# SmartDorm-ESP32.net
KiCad netlist of a schematic drawn in EasyEDA Pro
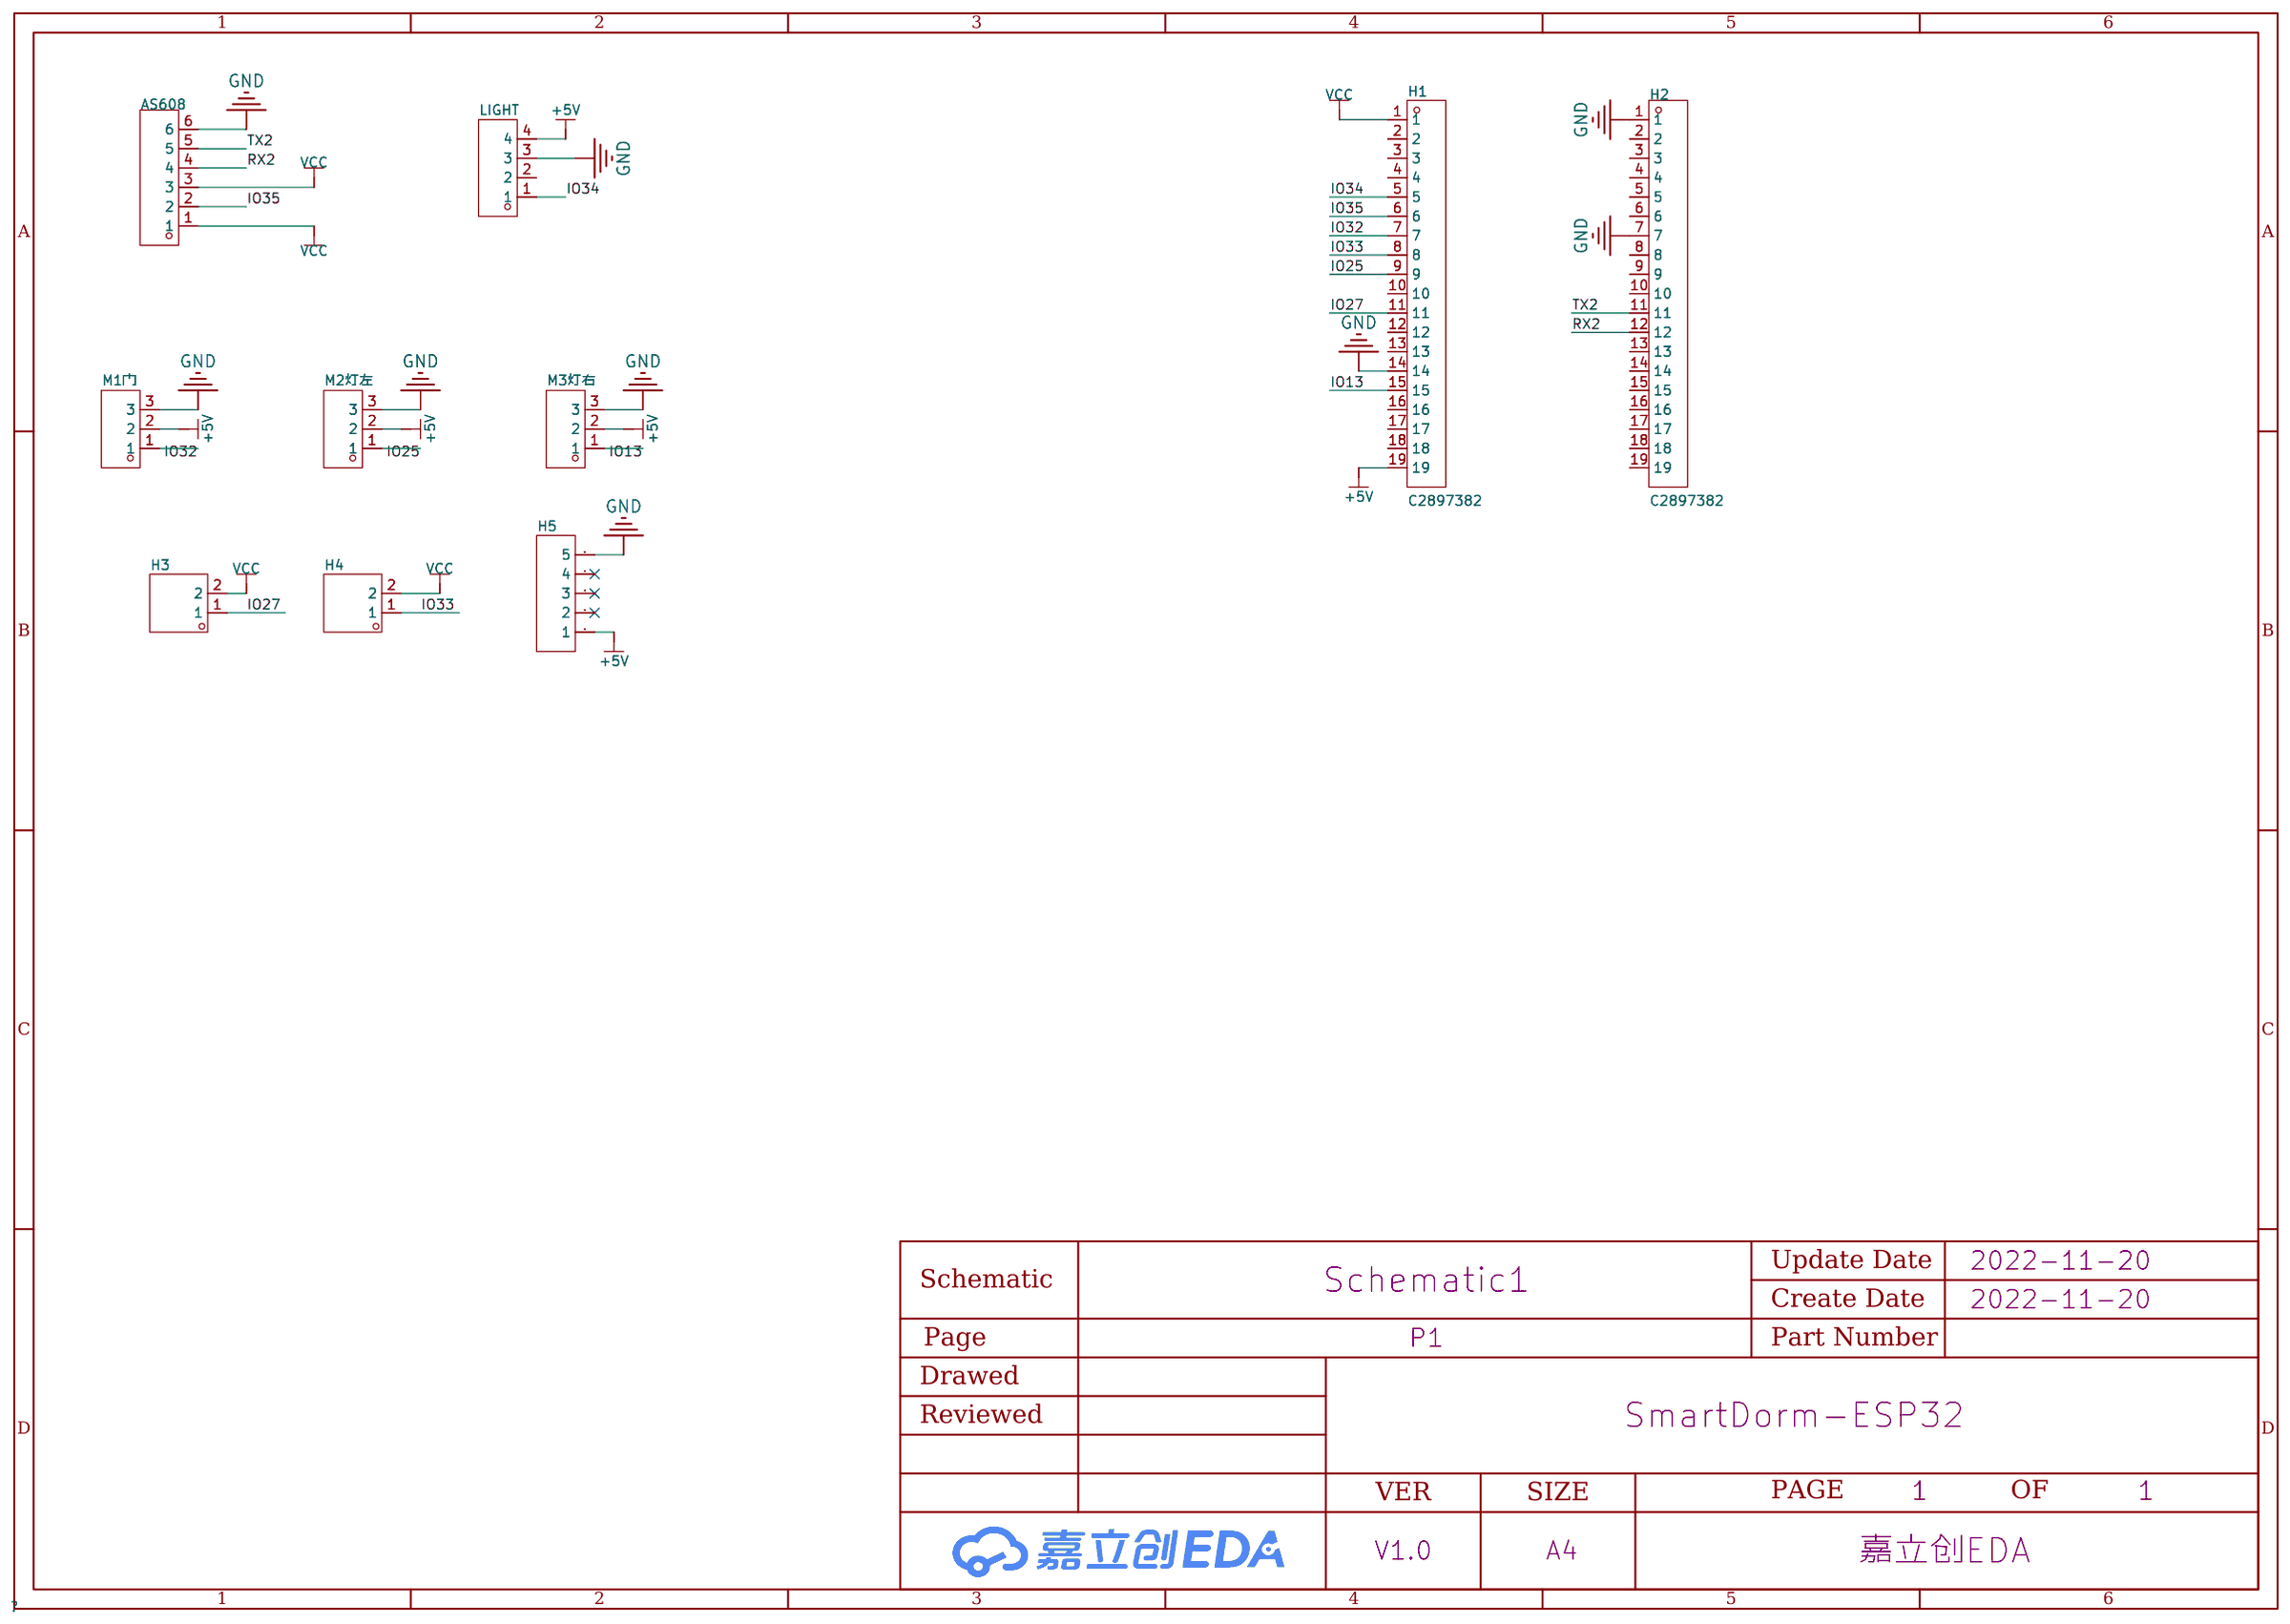
[diagram p0: schematic sheet]

(export (version "E")
  (design (tool "Eeschema 10.0.6"))
  (components
    (comp (ref "AS608")
      (value "~")
      (footprint "easyedapro:HDR-TH_6P-P2.54-V-F")
      (libsource (lib "easyedapro") (part "Header-Female-2.54_1x6"))
    )
    (comp (ref "H1")
      (value "C2897382")
      (footprint "easyedapro:HDR-TH_19P-P2.54-V-F")
      (libsource (lib "easyedapro") (part "HDR-F_2.54_1x19P"))
    )
    (comp (ref "H2")
      (value "C2897382")
      (footprint "easyedapro:HDR-TH_19P-P2.54-V-F")
      (libsource (lib "easyedapro") (part "HDR-F_2.54_1x19P"))
    )
    (comp (ref "H3")
      (value "~")
      (footprint "easyedapro:HDR-TH_2P-P2.54-V-M-1")
      (libsource (lib "easyedapro") (part "210S-1*2P L=11.6MMGold-plated black"))
    )
    (comp (ref "H4")
      (value "~")
      (footprint "easyedapro:HDR-TH_2P-P2.54-V-M-1")
      (libsource (lib "easyedapro") (part "210S-1*2P L=11.6MMGold-plated black"))
    )
    (comp (ref "H5")
      (value "~")
      (footprint "easyedapro:HDR-TH_5P-P2.54-V-F")
      (libsource (lib "easyedapro") (part "Header-Female-2.54_1x5"))
    )
    (comp (ref "LIGHT")
      (value "~")
      (footprint "easyedapro:HDR-TH_4P-P2.54-V-F")
      (libsource (lib "easyedapro") (part "2.54-1*4P母"))
    )
    (comp (ref "M1门")
      (value "~")
      (footprint "easyedapro:HDR-TH_3P-P2.54-V-M")
      (libsource (lib "easyedapro") (part "PZ254V-11-03P_C2937625"))
    )
    (comp (ref "M2灯左")
      (value "~")
      (footprint "easyedapro:HDR-TH_3P-P2.54-V-M")
      (libsource (lib "easyedapro") (part "PZ254V-11-03P_C2937625"))
    )
    (comp (ref "M3灯右")
      (value "~")
      (footprint "easyedapro:HDR-TH_3P-P2.54-V-M")
      (libsource (lib "easyedapro") (part "PZ254V-11-03P_C2937625"))
    )
  )
  (nets
    (net (code "1") (name "+5V") (class "Default")
      (node (ref "H1") (pin "19") (pinfunction "19_19") (pintype "input"))
      (node (ref "H5") (pin "1") (pinfunction "1_1") (pintype "input"))
      (node (ref "LIGHT") (pin "4") (pinfunction "4_4") (pintype "input"))
      (node (ref "M1门") (pin "2") (pinfunction "2_2") (pintype "input"))
      (node (ref "M2灯左") (pin "2") (pinfunction "2_2") (pintype "input"))
      (node (ref "M3灯右") (pin "2") (pinfunction "2_2") (pintype "input"))
    )
    (net (code "2") (name "/IO13") (class "Default")
      (node (ref "H1") (pin "15") (pinfunction "15_15") (pintype "input"))
      (node (ref "M3灯右") (pin "1") (pinfunction "1_1") (pintype "input"))
    )
    (net (code "3") (name "/IO25") (class "Default")
      (node (ref "H1") (pin "9") (pinfunction "9_9") (pintype "input"))
      (node (ref "M2灯左") (pin "1") (pinfunction "1_1") (pintype "input"))
    )
    (net (code "4") (name "/IO27") (class "Default")
      (node (ref "H1") (pin "11") (pinfunction "11_11") (pintype "input"))
      (node (ref "H3") (pin "1") (pinfunction "1_1") (pintype "input"))
    )
    (net (code "5") (name "/IO32") (class "Default")
      (node (ref "H1") (pin "7") (pinfunction "7_7") (pintype "input"))
      (node (ref "M1门") (pin "1") (pinfunction "1_1") (pintype "input"))
    )
    (net (code "6") (name "/IO33") (class "Default")
      (node (ref "H1") (pin "8") (pinfunction "8_8") (pintype "input"))
      (node (ref "H4") (pin "1") (pinfunction "1_1") (pintype "input"))
    )
    (net (code "7") (name "/IO34") (class "Default")
      (node (ref "H1") (pin "5") (pinfunction "5_5") (pintype "input"))
      (node (ref "LIGHT") (pin "1") (pinfunction "1_1") (pintype "input"))
    )
    (net (code "8") (name "/IO35") (class "Default")
      (node (ref "AS608") (pin "2") (pinfunction "2_2") (pintype "input"))
      (node (ref "H1") (pin "6") (pinfunction "6_6") (pintype "input"))
    )
    (net (code "9") (name "/RX2") (class "Default")
      (node (ref "AS608") (pin "4") (pinfunction "4_4") (pintype "input"))
      (node (ref "H2") (pin "12") (pinfunction "12_12") (pintype "input"))
    )
    (net (code "10") (name "/TX2") (class "Default")
      (node (ref "AS608") (pin "5") (pinfunction "5_5") (pintype "input"))
      (node (ref "H2") (pin "11") (pinfunction "11_11") (pintype "input"))
    )
    (net (code "11") (name "GND") (class "Default")
      (node (ref "AS608") (pin "6") (pinfunction "6_6") (pintype "input"))
      (node (ref "H1") (pin "14") (pinfunction "14_14") (pintype "input"))
      (node (ref "H2") (pin "1") (pinfunction "1_1") (pintype "input"))
      (node (ref "H2") (pin "7") (pinfunction "7_7") (pintype "input"))
      (node (ref "H5") (pin "5") (pinfunction "5_5") (pintype "input"))
      (node (ref "LIGHT") (pin "3") (pinfunction "3_3") (pintype "input"))
      (node (ref "M1门") (pin "3") (pinfunction "3_3") (pintype "input"))
      (node (ref "M2灯左") (pin "3") (pinfunction "3_3") (pintype "input"))
      (node (ref "M3灯右") (pin "3") (pinfunction "3_3") (pintype "input"))
    )
    (net (code "12") (name "VCC") (class "Default")
      (node (ref "AS608") (pin "1") (pinfunction "1_1") (pintype "input"))
      (node (ref "AS608") (pin "3") (pinfunction "3_3") (pintype "input"))
      (node (ref "H1") (pin "1") (pinfunction "1_1") (pintype "input"))
      (node (ref "H3") (pin "2") (pinfunction "2_2") (pintype "input"))
      (node (ref "H4") (pin "2") (pinfunction "2_2") (pintype "input"))
    )
    (net (code "13") (name "unconnected-(H1-Pad2)") (class "Default")
      (node (ref "H1") (pin "2") (pinfunction "2_2") (pintype "input"))
    )
    (net (code "14") (name "unconnected-(H1-Pad3)") (class "Default")
      (node (ref "H1") (pin "3") (pinfunction "3_3") (pintype "input"))
    )
    (net (code "15") (name "unconnected-(H1-Pad4)") (class "Default")
      (node (ref "H1") (pin "4") (pinfunction "4_4") (pintype "input"))
    )
    (net (code "16") (name "unconnected-(H1-Pad10)") (class "Default")
      (node (ref "H1") (pin "10") (pinfunction "10_10") (pintype "input"))
    )
    (net (code "17") (name "unconnected-(H1-Pad12)") (class "Default")
      (node (ref "H1") (pin "12") (pinfunction "12_12") (pintype "input"))
    )
    (net (code "18") (name "unconnected-(H1-Pad13)") (class "Default")
      (node (ref "H1") (pin "13") (pinfunction "13_13") (pintype "input"))
    )
    (net (code "19") (name "unconnected-(H1-Pad16)") (class "Default")
      (node (ref "H1") (pin "16") (pinfunction "16_16") (pintype "input"))
    )
    (net (code "20") (name "unconnected-(H1-Pad17)") (class "Default")
      (node (ref "H1") (pin "17") (pinfunction "17_17") (pintype "input"))
    )
    (net (code "21") (name "unconnected-(H1-Pad18)") (class "Default")
      (node (ref "H1") (pin "18") (pinfunction "18_18") (pintype "input"))
    )
    (net (code "22") (name "unconnected-(H2-Pad2)") (class "Default")
      (node (ref "H2") (pin "2") (pinfunction "2_2") (pintype "input"))
    )
    (net (code "23") (name "unconnected-(H2-Pad3)") (class "Default")
      (node (ref "H2") (pin "3") (pinfunction "3_3") (pintype "input"))
    )
    (net (code "24") (name "unconnected-(H2-Pad4)") (class "Default")
      (node (ref "H2") (pin "4") (pinfunction "4_4") (pintype "input"))
    )
    (net (code "25") (name "unconnected-(H2-Pad5)") (class "Default")
      (node (ref "H2") (pin "5") (pinfunction "5_5") (pintype "input"))
    )
    (net (code "26") (name "unconnected-(H2-Pad6)") (class "Default")
      (node (ref "H2") (pin "6") (pinfunction "6_6") (pintype "input"))
    )
    (net (code "27") (name "unconnected-(H2-Pad8)") (class "Default")
      (node (ref "H2") (pin "8") (pinfunction "8_8") (pintype "input"))
    )
    (net (code "28") (name "unconnected-(H2-Pad9)") (class "Default")
      (node (ref "H2") (pin "9") (pinfunction "9_9") (pintype "input"))
    )
    (net (code "29") (name "unconnected-(H2-Pad10)") (class "Default")
      (node (ref "H2") (pin "10") (pinfunction "10_10") (pintype "input"))
    )
    (net (code "30") (name "unconnected-(H2-Pad13)") (class "Default")
      (node (ref "H2") (pin "13") (pinfunction "13_13") (pintype "input"))
    )
    (net (code "31") (name "unconnected-(H2-Pad14)") (class "Default")
      (node (ref "H2") (pin "14") (pinfunction "14_14") (pintype "input"))
    )
    (net (code "32") (name "unconnected-(H2-Pad15)") (class "Default")
      (node (ref "H2") (pin "15") (pinfunction "15_15") (pintype "input"))
    )
    (net (code "33") (name "unconnected-(H2-Pad16)") (class "Default")
      (node (ref "H2") (pin "16") (pinfunction "16_16") (pintype "input"))
    )
    (net (code "34") (name "unconnected-(H2-Pad17)") (class "Default")
      (node (ref "H2") (pin "17") (pinfunction "17_17") (pintype "input"))
    )
    (net (code "35") (name "unconnected-(H2-Pad18)") (class "Default")
      (node (ref "H2") (pin "18") (pinfunction "18_18") (pintype "input"))
    )
    (net (code "36") (name "unconnected-(H2-Pad19)") (class "Default")
      (node (ref "H2") (pin "19") (pinfunction "19_19") (pintype "input"))
    )
    (net (code "37") (name "unconnected-(H5-Pad2)") (class "Default")
      (node (ref "H5") (pin "2") (pinfunction "2_2") (pintype "input+no_connect"))
    )
    (net (code "38") (name "unconnected-(H5-Pad3)") (class "Default")
      (node (ref "H5") (pin "3") (pinfunction "3_3") (pintype "input+no_connect"))
    )
    (net (code "39") (name "unconnected-(H5-Pad4)") (class "Default")
      (node (ref "H5") (pin "4") (pinfunction "4_4") (pintype "input+no_connect"))
    )
    (net (code "40") (name "unconnected-(LIGHT-Pad2)") (class "Default")
      (node (ref "LIGHT") (pin "2") (pinfunction "2_2") (pintype "input"))
    )
  )
)
